# SH9_-_CAN.net
KiCad netlist of a schematic drawn in Altium Designer
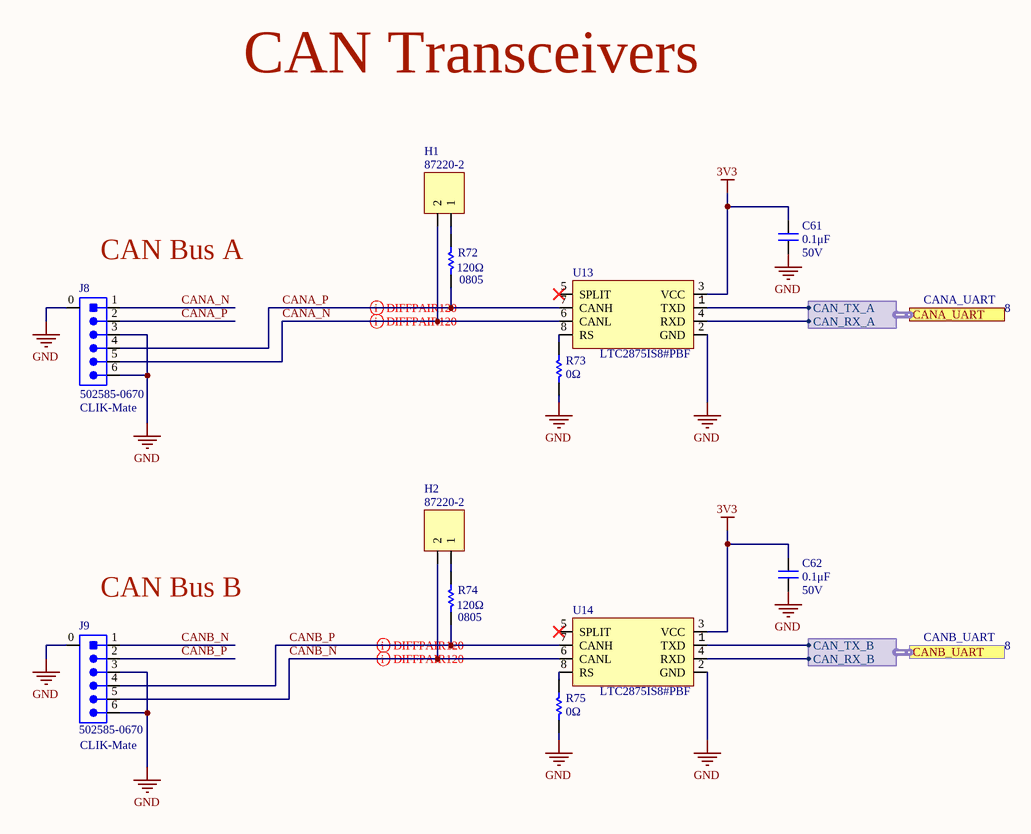
[diagram p0: SH9 - CAN.SchDoc]

(export (version "E")
  (design (tool "Eeschema 10.0.6"))
  (components
    (comp (ref "C61")
      (value "0.1μF")
      (footprint "CAP2012")
      (description "CAP CER 0.1UF 50V X7R 0805")
      (fields
        (field (name "VOLTAGE RATING") "50V")
        (field (name "TOLERANCE") "10%")
        (field (name "LCSC PART #") "C49678")
      )
      (libsource (lib "UWRT_Schematic_Library_2020") (part "CAP_0.1uF_50V_0805"))
    )
    (comp (ref "C62")
      (value "0.1μF")
      (footprint "CAP2012")
      (description "CAP CER 0.1UF 50V X7R 0805")
      (fields
        (field (name "VOLTAGE RATING") "50V")
        (field (name "TOLERANCE") "10%")
        (field (name "LCSC PART #") "C49678")
      )
      (libsource (lib "UWRT_Schematic_Library_2020") (part "CAP_0.1uF_50V_0805"))
    )
    (comp (ref "H1")
      (value "JUMPER_2")
      (footprint "HDR1X2")
      (description "HEADER 2X1")
      (fields (field (name "MANUFACTURER PART NUMBER 1") "87220-2"))
      (libsource (lib "UWRT_Schematic_Library_2020") (part "JUMPER_2"))
    )
    (comp (ref "H2")
      (value "JUMPER_2")
      (footprint "HDR1X2")
      (description "HEADER 2X1")
      (fields (field (name "MANUFACTURER PART NUMBER 1") "87220-2"))
      (libsource (lib "UWRT_Schematic_Library_2020") (part "JUMPER_2"))
    )
    (comp (ref "J8")
      (value "CON_6M_SM_RA_1.5mm")
      (footprint "MOLEX-5025850670")
      (description "CONN HEADER SMD RIGHT ANGLE 1.5 MM PITCH")
      (fields
        (field (name "MANUFACTOR NUMBER") "502585-0670")
        (field (name "MANUFACTURER") "Molex")
        (field (name "FAMILY") "CLIK-Mate")
      )
      (libsource (lib "UWRT_Schematic_Library_2020") (part "CON_6M_SM_RA_1.5mm"))
    )
    (comp (ref "J9")
      (value "CON_6M_SM_RA_1.5mm")
      (footprint "MOLEX-5025850670")
      (description "CONN HEADER SMD RIGHT ANGLE 1.5 MM PITCH")
      (fields
        (field (name "MANUFACTOR NUMBER") "502585-0670")
        (field (name "MANUFACTURER") "Molex")
        (field (name "FAMILY") "CLIK-Mate")
      )
      (libsource (lib "UWRT_Schematic_Library_2020") (part "CON_6M_SM_RA_1.5mm"))
    )
    (comp (ref "R72")
      (value "RES_120Ω_0805_1%")
      (footprint "RESC0805")
      (description "RES 120 OHM 1% 1/8W 0805")
      (fields
        (field (name "RESISTANCE") "120Ω")
        (field (name "LCSC PART #") "C17437")
        (field (name "PACKAGE/FOOTPRINT") "0805")
      )
      (libsource (lib "UWRT_Schematic_Library_2020") (part "RES_120Ω_0805_1%"))
    )
    (comp (ref "R73")
      (value "0Ω")
      (footprint "RESC0805")
      (description "RES 0 OHM JUMPER 1/8W 0805")
      (fields (field (name "LCSC PART #") "C17477") (field (name "Comment") "RES_0Ω_0805"))
      (libsource (lib "UWRT_Schematic_Library_2020") (part "RES_0Ω_0805"))
    )
    (comp (ref "R74")
      (value "RES_120Ω_0805_1%")
      (footprint "RESC0805")
      (description "RES 120 OHM 1% 1/8W 0805")
      (fields
        (field (name "RESISTANCE") "120Ω")
        (field (name "LCSC PART #") "C17437")
        (field (name "PACKAGE/FOOTPRINT") "0805")
      )
      (libsource (lib "UWRT_Schematic_Library_2020") (part "RES_120Ω_0805_1%"))
    )
    (comp (ref "R75")
      (value "0Ω")
      (footprint "RESC0805")
      (description "RES 0 OHM JUMPER 1/8W 0805")
      (fields (field (name "LCSC PART #") "C17477") (field (name "Comment") "RES_0Ω_0805"))
      (libsource (lib "UWRT_Schematic_Library_2020") (part "RES_0Ω_0805"))
    )
    (comp (ref "U13")
      (value "LTC2875")
      (footprint "LT-S8_N")
      (description "IC TXRX CAN 4MBPS 8SO")
      (fields
        (field (name "MANUFACTURER PART NUMBER 1") "LTC2875IS8#PBF")
        (field (name "LCSC PART #") "C117076")
      )
      (libsource (lib "UWRT_Schematic_Library_2020") (part "LTC2875"))
    )
    (comp (ref "U14")
      (value "LTC2875")
      (footprint "LT-S8_N")
      (description "IC TXRX CAN 4MBPS 8SO")
      (fields
        (field (name "MANUFACTURER PART NUMBER 1") "LTC2875IS8#PBF")
        (field (name "LCSC PART #") "C117076")
      )
      (libsource (lib "UWRT_Schematic_Library_2020") (part "LTC2875"))
    )
  )
  (nets
    (net (code "3") (name "/CANA_N") (class "Default")
      (node (ref "H1") (pin "2") (pinfunction "2_2") (pintype "passive"))
      (node (ref "J8") (pin "1") (pinfunction "1_1") (pintype "passive"))
      (node (ref "J8") (pin "5") (pinfunction "5_5") (pintype "passive"))
      (node (ref "U13") (pin "6") (pinfunction "CANL_6") (pintype "passive"))
    )
    (net (code "4") (name "/CANA_P") (class "Default")
      (node (ref "J8") (pin "2") (pinfunction "2_2") (pintype "passive"))
      (node (ref "J8") (pin "4") (pinfunction "4_4") (pintype "passive"))
      (node (ref "R72") (pin "1") (pinfunction "1_1") (pintype "passive"))
      (node (ref "U13") (pin "7") (pinfunction "CANH_7") (pintype "passive"))
    )
    (net (code "5") (name "/CANB_N") (class "Default")
      (node (ref "H2") (pin "2") (pinfunction "2_2") (pintype "passive"))
      (node (ref "J9") (pin "1") (pinfunction "1_1") (pintype "passive"))
      (node (ref "J9") (pin "5") (pinfunction "5_5") (pintype "passive"))
      (node (ref "U14") (pin "6") (pinfunction "CANL_6") (pintype "passive"))
    )
    (net (code "6") (name "/CANB_P") (class "Default")
      (node (ref "J9") (pin "2") (pinfunction "2_2") (pintype "passive"))
      (node (ref "J9") (pin "4") (pinfunction "4_4") (pintype "passive"))
      (node (ref "R74") (pin "1") (pinfunction "1_1") (pintype "passive"))
      (node (ref "U14") (pin "7") (pinfunction "CANH_7") (pintype "passive"))
    )
    (net (code "7") (name "/CAN_RX_A") (class "Default")
      (node (ref "U13") (pin "4") (pinfunction "RXD_4") (pintype "passive"))
    )
    (net (code "8") (name "/CAN_RX_B") (class "Default")
      (node (ref "U14") (pin "4") (pinfunction "RXD_4") (pintype "passive"))
    )
    (net (code "9") (name "/CAN_TX_A") (class "Default")
      (node (ref "U13") (pin "1") (pinfunction "TXD_1") (pintype "passive"))
    )
    (net (code "10") (name "/CAN_TX_B") (class "Default")
      (node (ref "U14") (pin "1") (pinfunction "TXD_1") (pintype "passive"))
    )
    (net (code "13") (name "3V3") (class "Default")
      (node (ref "C61") (pin "1") (pinfunction "1_1") (pintype "passive"))
      (node (ref "C62") (pin "1") (pinfunction "1_1") (pintype "passive"))
      (node (ref "U13") (pin "3") (pinfunction "VCC_3") (pintype "passive"))
      (node (ref "U14") (pin "3") (pinfunction "VCC_3") (pintype "passive"))
    )
    (net (code "14") (name "GND") (class "Default")
      (node (ref "C61") (pin "2") (pinfunction "2_2") (pintype "passive"))
      (node (ref "C62") (pin "2") (pinfunction "2_2") (pintype "passive"))
      (node (ref "J8") (pin "0") (pinfunction "0_0") (pintype "passive"))
      (node (ref "J8") (pin "3") (pinfunction "3_3") (pintype "passive"))
      (node (ref "J8") (pin "6") (pinfunction "6_6") (pintype "passive"))
      (node (ref "J9") (pin "0") (pinfunction "0_0") (pintype "passive"))
      (node (ref "J9") (pin "3") (pinfunction "3_3") (pintype "passive"))
      (node (ref "J9") (pin "6") (pinfunction "6_6") (pintype "passive"))
      (node (ref "R73") (pin "1") (pinfunction "1_1") (pintype "passive"))
      (node (ref "R75") (pin "1") (pinfunction "1_1") (pintype "passive"))
      (node (ref "U13") (pin "2") (pinfunction "GND_2") (pintype "passive"))
      (node (ref "U14") (pin "2") (pinfunction "GND_2") (pintype "passive"))
    )
    (net (code "15") (name "Net-(H1-Pad1)") (class "Default")
      (node (ref "H1") (pin "1") (pinfunction "1_1") (pintype "passive"))
      (node (ref "R72") (pin "2") (pinfunction "2_2") (pintype "passive"))
    )
    (net (code "16") (name "Net-(H2-Pad1)") (class "Default")
      (node (ref "H2") (pin "1") (pinfunction "1_1") (pintype "passive"))
      (node (ref "R74") (pin "2") (pinfunction "2_2") (pintype "passive"))
    )
    (net (code "17") (name "Net-(U13-RS)") (class "Default")
      (node (ref "R73") (pin "2") (pinfunction "2_2") (pintype "passive"))
      (node (ref "U13") (pin "8") (pinfunction "RS_8") (pintype "passive"))
    )
    (net (code "18") (name "Net-(U14-RS)") (class "Default")
      (node (ref "R75") (pin "2") (pinfunction "2_2") (pintype "passive"))
      (node (ref "U14") (pin "8") (pinfunction "RS_8") (pintype "passive"))
    )
    (net (code "19") (name "unconnected-(U13-SPLIT-Pad5)") (class "Default")
      (node (ref "U13") (pin "5") (pinfunction "SPLIT_5") (pintype "passive+no_connect"))
    )
    (net (code "20") (name "unconnected-(U14-SPLIT-Pad5)") (class "Default")
      (node (ref "U14") (pin "5") (pinfunction "SPLIT_5") (pintype "passive+no_connect"))
    )
  )
)
